# Mother_board_power.net
KiCad netlist of a schematic drawn in Altium Designer
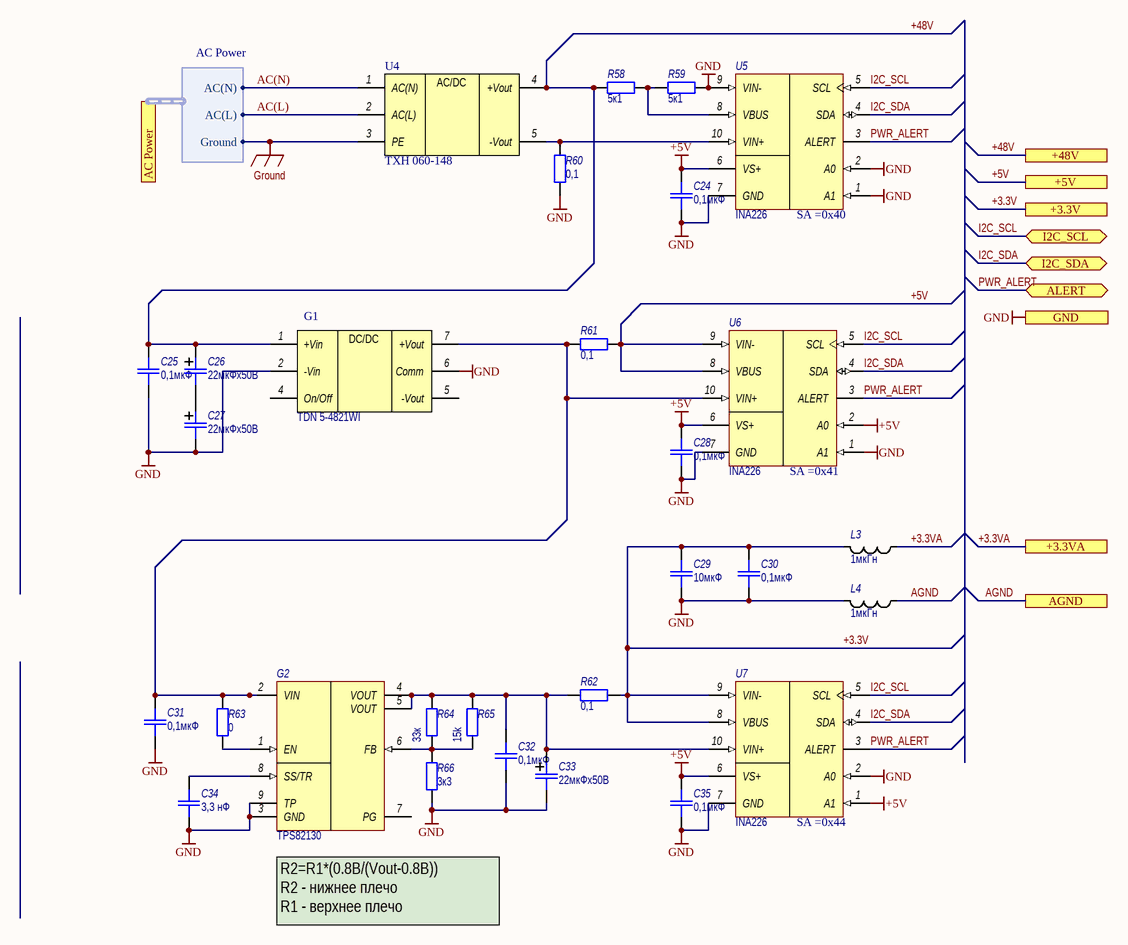
[diagram p0: Mother_board_power.SchDoc]

(export (version "E")
  (design (tool "Eeschema 10.0.6"))
  (components
    (comp (ref "C24")
      (value "0,1мкФ")
      (footprint "SMD_0805")
      (description "Capacitor")
      (libsource (lib "*") (part "Capacitor"))
    )
    (comp (ref "C25")
      (value "0,1мкФ")
      (footprint "SMD_0805")
      (description "Capacitor")
      (libsource (lib "*") (part "Capacitor"))
    )
    (comp (ref "C26")
      (value "22мкФх50В")
      (footprint "SMD_size_B")
      (description "Polarized capacitor")
      (libsource (lib "*") (part "Capacitor_pol"))
    )
    (comp (ref "C27")
      (value "22мкФх50В")
      (footprint "SMD_size_B")
      (description "Polarized capacitor")
      (libsource (lib "*") (part "Capacitor_pol"))
    )
    (comp (ref "C28")
      (value "0,1мкФ")
      (footprint "SMD_0805")
      (description "Capacitor")
      (libsource (lib "*") (part "Capacitor"))
    )
    (comp (ref "C29")
      (value "10мкФ")
      (footprint "SMD_0805")
      (description "Capacitor")
      (libsource (lib "*") (part "Capacitor"))
    )
    (comp (ref "C30")
      (value "0,1мкФ")
      (footprint "SMD_0805")
      (description "Capacitor")
      (libsource (lib "*") (part "Capacitor"))
    )
    (comp (ref "C31")
      (value "0,1мкФ")
      (footprint "SMD_0805")
      (description "Capacitor")
      (libsource (lib "*") (part "Capacitor"))
    )
    (comp (ref "C32")
      (value "0,1мкФ")
      (footprint "SMD_0805")
      (description "Capacitor")
      (libsource (lib "*") (part "Capacitor"))
    )
    (comp (ref "C33")
      (value "22мкФх50В")
      (footprint "SMD_size_B")
      (description "Polarized capacitor")
      (libsource (lib "*") (part "Capacitor_pol"))
    )
    (comp (ref "C34")
      (value "3,3 нФ")
      (footprint "SMD_0805")
      (description "Capacitor")
      (libsource (lib "*") (part "Capacitor"))
    )
    (comp (ref "C35")
      (value "0,1мкФ")
      (footprint "SMD_0805")
      (description "Capacitor")
      (libsource (lib "*") (part "Capacitor"))
    )
    (comp (ref "G1")
      (value "TDN 5-4821")
      (footprint "TDN_5_WISM")
      (description "DC/DC converter")
      (fields (field (name "НАИМЕНОВАНИЕ") "TDN 5-4821WI"))
      (libsource (lib "*") (part "TDN_5"))
    )
    (comp (ref "G2")
      (value "TPS82130")
      (footprint "uSiL-8")
      (description "17-V Input 3-A Step-Down Converter MicroSiP™ Module with Integrated Inductor")
      (fields (field (name "НАИМЕНОВАНИЕ") "TPS82130"))
      (libsource (lib "*") (part "TPS82130"))
    )
    (comp (ref "L3")
      (value "1мкГн")
      (footprint "SMD_0805")
      (description "Inductor")
      (libsource (lib "Passive") (part "Inductor"))
    )
    (comp (ref "L4")
      (value "1мкГн")
      (footprint "SMD_0805")
      (description "Inductor")
      (libsource (lib "Passive") (part "Inductor"))
    )
    (comp (ref "R58")
      (value "5к1")
      (footprint "SMD_0805")
      (description "Resistor")
      (libsource (lib "*") (part "Resistor"))
    )
    (comp (ref "R59")
      (value "5к1")
      (footprint "SMD_0805")
      (description "Resistor")
      (libsource (lib "*") (part "Resistor"))
    )
    (comp (ref "R60")
      (value "0,1")
      (footprint "SMD_0805")
      (description "Resistor")
      (libsource (lib "") (part "Resistor_2"))
    )
    (comp (ref "R61")
      (value "0,1")
      (footprint "SMD_0805")
      (description "Resistor")
      (libsource (lib "*") (part "Resistor"))
    )
    (comp (ref "R62")
      (value "0,1")
      (footprint "SMD_0805")
      (description "Resistor")
      (libsource (lib "*") (part "Resistor"))
    )
    (comp (ref "R63")
      (value "0")
      (footprint "SMD_0805")
      (description "Resistor")
      (libsource (lib "") (part "Resistor_2"))
    )
    (comp (ref "R64")
      (value "33к")
      (footprint "SMD_0805")
      (description "Resistor")
      (libsource (lib "") (part "Resistor_1"))
    )
    (comp (ref "R65")
      (value "15k")
      (footprint "SMD_0805")
      (description "Resistor")
      (libsource (lib "") (part "Resistor_1"))
    )
    (comp (ref "R66")
      (value "3к3")
      (footprint "SMD_0805")
      (description "Resistor")
      (libsource (lib "") (part "Resistor_1"))
    )
    (comp (ref "U4")
      (value "TXH 060-148")
      (footprint "TXH 060-148 (2)")
      (description "AC/DC Power Supply")
      (libsource (lib "TXH 060-148") (part "TXH 060-148"))
    )
    (comp (ref "U5")
      (value "INA226")
      (footprint "VSSOP-10")
      (description "High- or Low-Side Measurement, Bidirectional Current and Power Monitor With I2C Interface")
      (fields (field (name "НАИМЕНОВАНИЕ") "INA226") (field (name "ADRESS") "SA =0x40"))
      (libsource (lib "Power_Monitor") (part "INA226"))
    )
    (comp (ref "U6")
      (value "INA226")
      (footprint "VSSOP-10")
      (description "High- or Low-Side Measurement, Bidirectional Current and Power Monitor With I2C Interface")
      (fields (field (name "НАИМЕНОВАНИЕ") "INA226") (field (name "ADRESS") "SA =0x41"))
      (libsource (lib "Power_Monitor") (part "INA226"))
    )
    (comp (ref "U7")
      (value "INA226")
      (footprint "VSSOP-10")
      (description "High- or Low-Side Measurement, Bidirectional Current and Power Monitor With I2C Interface")
      (fields (field (name "НАИМЕНОВАНИЕ") "INA226") (field (name "ADRESS") "SA =0x44"))
      (libsource (lib "Power_Monitor") (part "INA226"))
    )
  )
  (nets
    (net (code "3") (name "+5V") (class "Default")
      (node (ref "C24") (pin "2") (pinfunction "2_2") (pintype "passive"))
      (node (ref "C28") (pin "2") (pinfunction "2_2") (pintype "passive"))
      (node (ref "C35") (pin "2") (pinfunction "2_2") (pintype "passive"))
      (node (ref "R61") (pin "2") (pinfunction "2_2") (pintype "passive"))
      (node (ref "U5") (pin "6") (pinfunction "VS+_6") (pintype "power_in"))
      (node (ref "U6") (pin "2") (pinfunction "A0_2") (pintype "input"))
      (node (ref "U6") (pin "6") (pinfunction "VS+_6") (pintype "power_in"))
      (node (ref "U6") (pin "8") (pinfunction "VBUS_8") (pintype "input"))
      (node (ref "U6") (pin "9") (pinfunction "VIN-_9") (pintype "input"))
      (node (ref "U7") (pin "1") (pinfunction "A1_1") (pintype "input"))
      (node (ref "U7") (pin "6") (pinfunction "VS+_6") (pintype "power_in"))
    )
    (net (code "4") (name "/+3.3V") (class "Default")
      (node (ref "C29") (pin "2") (pinfunction "2_2") (pintype "passive"))
      (node (ref "C30") (pin "2") (pinfunction "2_2") (pintype "passive"))
      (node (ref "L3") (pin "2") (pinfunction "2_2") (pintype "passive"))
      (node (ref "R62") (pin "2") (pinfunction "2_2") (pintype "passive"))
      (node (ref "U7") (pin "8") (pinfunction "VBUS_8") (pintype "input"))
      (node (ref "U7") (pin "9") (pinfunction "VIN-_9") (pintype "input"))
    )
    (net (code "5") (name "/+3.3VA") (class "Default")
      (node (ref "L3") (pin "1") (pinfunction "1_1") (pintype "passive"))
    )
    (net (code "6") (name "/+48V") (class "Default")
      (node (ref "C25") (pin "2") (pinfunction "2_2") (pintype "passive"))
      (node (ref "C26") (pin "1") (pinfunction "1_1") (pintype "passive"))
      (node (ref "G1") (pin "1") (pinfunction "+Vin_1") (pintype "power_in"))
      (node (ref "R58") (pin "1") (pinfunction "1_1") (pintype "passive"))
      (node (ref "U4") (pin "4") (pinfunction "+Vout_4") (pintype "power_in"))
    )
    (net (code "7") (name "/AC(L)") (class "Default")
      (node (ref "U4") (pin "2") (pinfunction "AC(L)_2") (pintype "power_in"))
    )
    (net (code "8") (name "/AC(N)") (class "Default")
      (node (ref "U4") (pin "1") (pinfunction "AC(N)_1") (pintype "power_in"))
    )
    (net (code "9") (name "/AGND") (class "Default")
      (node (ref "L4") (pin "1") (pinfunction "1_1") (pintype "passive"))
    )
    (net (code "10") (name "/I2C_SCL") (class "Default")
      (node (ref "U5") (pin "5") (pinfunction "SCL_5") (pintype "input"))
      (node (ref "U6") (pin "5") (pinfunction "SCL_5") (pintype "input"))
      (node (ref "U7") (pin "5") (pinfunction "SCL_5") (pintype "input"))
    )
    (net (code "11") (name "/I2C_SDA") (class "Default")
      (node (ref "U5") (pin "4") (pinfunction "SDA_4") (pintype "bidirectional"))
      (node (ref "U6") (pin "4") (pinfunction "SDA_4") (pintype "bidirectional"))
      (node (ref "U7") (pin "4") (pinfunction "SDA_4") (pintype "bidirectional"))
    )
    (net (code "12") (name "/PWR_ALERT") (class "Default")
      (node (ref "U5") (pin "3") (pinfunction "ALERT_3") (pintype "open_collector"))
      (node (ref "U6") (pin "3") (pinfunction "ALERT_3") (pintype "open_collector"))
      (node (ref "U7") (pin "3") (pinfunction "ALERT_3") (pintype "open_collector"))
    )
    (net (code "14") (name "GND") (class "Default")
      (node (ref "C24") (pin "1") (pinfunction "1_1") (pintype "passive"))
      (node (ref "C25") (pin "1") (pinfunction "1_1") (pintype "passive"))
      (node (ref "C27") (pin "2") (pinfunction "2_2") (pintype "passive"))
      (node (ref "C28") (pin "1") (pinfunction "1_1") (pintype "passive"))
      (node (ref "C29") (pin "1") (pinfunction "1_1") (pintype "passive"))
      (node (ref "C30") (pin "1") (pinfunction "1_1") (pintype "passive"))
      (node (ref "C31") (pin "1") (pinfunction "1_1") (pintype "passive"))
      (node (ref "C32") (pin "1") (pinfunction "1_1") (pintype "passive"))
      (node (ref "C33") (pin "2") (pinfunction "2_2") (pintype "passive"))
      (node (ref "C34") (pin "1") (pinfunction "1_1") (pintype "passive"))
      (node (ref "C35") (pin "1") (pinfunction "1_1") (pintype "passive"))
      (node (ref "G1") (pin "2") (pinfunction "-Vin_2") (pintype "power_in"))
      (node (ref "G1") (pin "6") (pinfunction "Comm_6") (pintype "power_in"))
      (node (ref "G2") (pin "3") (pinfunction "GND_3") (pintype "power_in"))
      (node (ref "G2") (pin "9") (pinfunction "TP_9") (pintype "power_in"))
      (node (ref "L4") (pin "2") (pinfunction "2_2") (pintype "passive"))
      (node (ref "R59") (pin "2") (pinfunction "2_2") (pintype "passive"))
      (node (ref "R60") (pin "1") (pinfunction "1_1") (pintype "passive"))
      (node (ref "R66") (pin "2") (pinfunction "2_2") (pintype "passive"))
      (node (ref "U5") (pin "1") (pinfunction "A1_1") (pintype "input"))
      (node (ref "U5") (pin "2") (pinfunction "A0_2") (pintype "input"))
      (node (ref "U5") (pin "7") (pinfunction "GND_7") (pintype "power_in"))
      (node (ref "U5") (pin "9") (pinfunction "VIN-_9") (pintype "input"))
      (node (ref "U6") (pin "1") (pinfunction "A1_1") (pintype "input"))
      (node (ref "U6") (pin "7") (pinfunction "GND_7") (pintype "power_in"))
      (node (ref "U7") (pin "2") (pinfunction "A0_2") (pintype "input"))
      (node (ref "U7") (pin "7") (pinfunction "GND_7") (pintype "power_in"))
    )
    (net (code "15") (name "Ground") (class "Default")
      (node (ref "U4") (pin "3") (pinfunction "PE_3") (pintype "open_collector"))
    )
    (net (code "16") (name "Net-(C26-Pad2)") (class "Default")
      (node (ref "C26") (pin "2") (pinfunction "2_2") (pintype "passive"))
      (node (ref "C27") (pin "1") (pinfunction "1_1") (pintype "passive"))
    )
    (net (code "17") (name "Net-(G1-+Vout)") (class "Default")
      (node (ref "C31") (pin "2") (pinfunction "2_2") (pintype "passive"))
      (node (ref "G1") (pin "7") (pinfunction "+Vout_7") (pintype "power_in"))
      (node (ref "G2") (pin "2") (pinfunction "VIN_2") (pintype "power_in"))
      (node (ref "R61") (pin "1") (pinfunction "1_1") (pintype "passive"))
      (node (ref "R63") (pin "2") (pinfunction "2_2") (pintype "passive"))
      (node (ref "U6") (pin "10") (pinfunction "VIN+_10") (pintype "input"))
    )
    (net (code "18") (name "Net-(G2-EN)") (class "Default")
      (node (ref "G2") (pin "1") (pinfunction "EN_1") (pintype "input"))
      (node (ref "R63") (pin "1") (pinfunction "1_1") (pintype "passive"))
    )
    (net (code "19") (name "Net-(G2-FB)") (class "Default")
      (node (ref "G2") (pin "6") (pinfunction "FB_6") (pintype "input"))
      (node (ref "R64") (pin "2") (pinfunction "2_2") (pintype "passive"))
      (node (ref "R65") (pin "2") (pinfunction "2_2") (pintype "passive"))
      (node (ref "R66") (pin "1") (pinfunction "1_1") (pintype "passive"))
    )
    (net (code "20") (name "Net-(G2-SS{slash}TR)") (class "Default")
      (node (ref "C34") (pin "2") (pinfunction "2_2") (pintype "passive"))
      (node (ref "G2") (pin "8") (pinfunction "SS/TR_8") (pintype "input"))
    )
    (net (code "21") (name "Net-(U4--Vout)") (class "Default")
      (node (ref "R60") (pin "2") (pinfunction "2_2") (pintype "passive"))
      (node (ref "U4") (pin "5") (pinfunction "-Vout_5") (pintype "power_in"))
      (node (ref "U5") (pin "10") (pinfunction "VIN+_10") (pintype "input"))
    )
    (net (code "22") (name "Net-(U5-VBUS)") (class "Default")
      (node (ref "R58") (pin "2") (pinfunction "2_2") (pintype "passive"))
      (node (ref "R59") (pin "1") (pinfunction "1_1") (pintype "passive"))
      (node (ref "U5") (pin "8") (pinfunction "VBUS_8") (pintype "input"))
    )
    (net (code "23") (name "Net-(U7-VIN+)") (class "Default")
      (node (ref "C32") (pin "2") (pinfunction "2_2") (pintype "passive"))
      (node (ref "C33") (pin "1") (pinfunction "1_1") (pintype "passive"))
      (node (ref "G2") (pin "4") (pinfunction "VOUT_4") (pintype "power_in"))
      (node (ref "G2") (pin "5") (pinfunction "VOUT_5") (pintype "power_in"))
      (node (ref "R62") (pin "1") (pinfunction "1_1") (pintype "passive"))
      (node (ref "R64") (pin "1") (pinfunction "1_1") (pintype "passive"))
      (node (ref "R65") (pin "1") (pinfunction "1_1") (pintype "passive"))
      (node (ref "U7") (pin "10") (pinfunction "VIN+_10") (pintype "input"))
    )
    (net (code "24") (name "unconnected-(G1--Vout-Pad5)") (class "Default")
      (node (ref "G1") (pin "5") (pinfunction "-Vout_5") (pintype "power_in"))
    )
    (net (code "25") (name "unconnected-(G1-On{slash}Off-Pad4)") (class "Default")
      (node (ref "G1") (pin "4") (pinfunction "On/Off_4") (pintype "open_collector"))
    )
    (net (code "26") (name "unconnected-(G2-PG-Pad7)") (class "Default")
      (node (ref "G2") (pin "7") (pinfunction "PG_7") (pintype "open_collector"))
    )
  )
)
